# Motor_Interface.net
KiCad netlist of a schematic drawn in Altium Designer
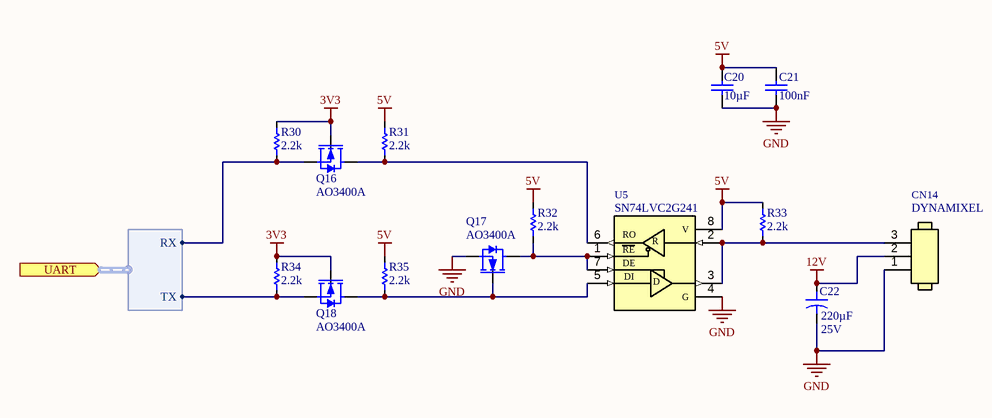
[diagram p0: Motor Interface.SchDoc]

(export (version "E")
  (design (tool "Eeschema 10.0.6"))
  (components
    (comp (ref "C20")
      (value "10µF")
      (footprint "CAP_CHIP_0603")
      (description "0603 Multilayer Ceramic Capacitors MLCC")
      (fields (field (name "PARTNUMBER") "CL10A106MA8NRNC") (field (name "TOLERANCE") "20%"))
      (libsource (lib "Sainsbury Wellcome Centre") (part "Cap"))
    )
    (comp (ref "C21")
      (value "100nF")
      (footprint "CAP_CHIP_0603")
      (description "0603 Multilayer Ceramic Capacitors MLCC")
      (fields (field (name "TOLERANCE") "10%") (field (name "PARTNUMBER") "CC0603KRX7R9BB104"))
      (libsource (lib "Sainsbury Wellcome Centre") (part "Cap"))
    )
    (comp (ref "C22")
      (value "220µF")
      (footprint "ECAP_SMD_6.3")
      (description "25V 220uF ±20% SMD,D6.3xL7.7mm Solid Capacitors")
      (fields
        (field (name "VOLTAGE RATING") "25V")
        (field (name "PARTNUMBER") "HV1E477M0810PZ")
        (field (name "TOLERANCE") "20%")
      )
      (libsource (lib "Sainsbury Wellcome Centre") (part "Cap Pol 2"))
    )
    (comp (ref "CN14")
      (value "DYNAMIXEL")
      (footprint "EH_90_1X3P")
      (description "Conn Shrouded Header (3 Sides) HDR 3 POS 2.5mm Solder RA Side Entry Thru-Hole Box")
      (fields (field (name "PARTNUMBER") "S3B-EH(LF)(SN)"))
      (libsource (lib "Sainsbury Wellcome Centre") (part "Wire to Board 1x3"))
    )
    (comp (ref "Q16")
      (value "AO3400A")
      (footprint "SOT23")
      (description "30V 5.7A 26.5mΩ@10V,5.7A 1.4W 1.5V@250uA 1 NChannel SOT-23-3L MOSFETs")
      (fields (field (name "PARTNUMBER") "AO3400A"))
      (libsource (lib "Sainsbury Wellcome Centre") (part "NMOS"))
    )
    (comp (ref "Q17")
      (value "AO3400A")
      (footprint "SOT23")
      (description "30V 5.7A 26.5mΩ@10V,5.7A 1.4W 1.5V@250uA 1 NChannel SOT-23-3L MOSFETs")
      (fields (field (name "PARTNUMBER") "AO3400A"))
      (libsource (lib "Sainsbury Wellcome Centre") (part "NMOS"))
    )
    (comp (ref "Q18")
      (value "AO3400A")
      (footprint "SOT23")
      (description "30V 5.7A 26.5mΩ@10V,5.7A 1.4W 1.5V@250uA 1 NChannel SOT-23-3L MOSFETs")
      (fields (field (name "PARTNUMBER") "AO3400A"))
      (libsource (lib "Sainsbury Wellcome Centre") (part "NMOS"))
    )
    (comp (ref "R30")
      (value "2.2k")
      (footprint "RES_CHIP_0603")
      (description "100mW Thick Film Resistors 75V ±100ppm/℃ ±1% 0603 Chip Resistor")
      (fields (field (name "PARTNUMBER") "0603WAF2201T5E") (field (name "TOLERANCE") "1%"))
      (libsource (lib "Sainsbury Wellcome Centre") (part "Res"))
    )
    (comp (ref "R31")
      (value "2.2k")
      (footprint "RES_CHIP_0603")
      (description "100mW Thick Film Resistors 75V ±100ppm/℃ ±1% 0603 Chip Resistor")
      (fields (field (name "PARTNUMBER") "0603WAF2201T5E") (field (name "TOLERANCE") "1%"))
      (libsource (lib "Sainsbury Wellcome Centre") (part "Res"))
    )
    (comp (ref "R32")
      (value "2.2k")
      (footprint "RES_CHIP_0603")
      (description "100mW Thick Film Resistors 75V ±100ppm/℃ ±1% 0603 Chip Resistor")
      (fields (field (name "PARTNUMBER") "0603WAF2201T5E") (field (name "TOLERANCE") "1%"))
      (libsource (lib "Sainsbury Wellcome Centre") (part "Res"))
    )
    (comp (ref "R33")
      (value "2.2k")
      (footprint "RES_CHIP_0603")
      (description "100mW Thick Film Resistors 75V ±100ppm/℃ ±1% 0603 Chip Resistor")
      (fields (field (name "PARTNUMBER") "0603WAF2201T5E") (field (name "TOLERANCE") "1%"))
      (libsource (lib "Sainsbury Wellcome Centre") (part "Res"))
    )
    (comp (ref "R34")
      (value "2.2k")
      (footprint "RES_CHIP_0603")
      (description "100mW Thick Film Resistors 75V ±100ppm/℃ ±1% 0603 Chip Resistor")
      (fields (field (name "PARTNUMBER") "0603WAF2201T5E") (field (name "TOLERANCE") "1%"))
      (libsource (lib "Sainsbury Wellcome Centre") (part "Res"))
    )
    (comp (ref "R35")
      (value "2.2k")
      (footprint "RES_CHIP_0603")
      (description "100mW Thick Film Resistors 75V ±100ppm/℃ ±1% 0603 Chip Resistor")
      (fields (field (name "PARTNUMBER") "0603WAF2201T5E") (field (name "TOLERANCE") "1%"))
      (libsource (lib "Sainsbury Wellcome Centre") (part "Res"))
    )
    (comp (ref "U5")
      (value "SN74LVC2G241")
      (footprint "VSSOP8_2X2.3_0.5E")
      (description "Buffer/Line Driver 2-CH Non-Inverting 3-ST CMOS 8-Pin VSSOP T/R")
      (fields (field (name "PARTNUMBER") "SN74LVC2G241DCUR"))
      (libsource (lib "Sainsbury Wellcome Centre") (part "SN74LVC2G241"))
    )
  )
  (nets
    (net (code "3") (name "3V3") (class "Default")
      (node (ref "Q16") (pin "1") (pinfunction "G_1") (pintype "passive"))
      (node (ref "Q18") (pin "1") (pinfunction "G_1") (pintype "passive"))
      (node (ref "R30") (pin "2") (pinfunction "2_2") (pintype "passive"))
      (node (ref "R34") (pin "2") (pinfunction "2_2") (pintype "passive"))
    )
    (net (code "4") (name "5V") (class "Default")
      (node (ref "C20") (pin "2") (pinfunction "2_2") (pintype "passive"))
      (node (ref "C21") (pin "2") (pinfunction "2_2") (pintype "passive"))
      (node (ref "R31") (pin "2") (pinfunction "2_2") (pintype "passive"))
      (node (ref "R32") (pin "2") (pinfunction "2_2") (pintype "passive"))
      (node (ref "R33") (pin "2") (pinfunction "2_2") (pintype "passive"))
      (node (ref "R35") (pin "2") (pinfunction "2_2") (pintype "passive"))
      (node (ref "U5") (pin "8") (pinfunction "V_8") (pintype "power_in"))
    )
    (net (code "5") (name "12V") (class "Default")
      (node (ref "C22") (pin "1") (pinfunction "1_1") (pintype "passive"))
      (node (ref "CN14") (pin "2") (pinfunction "2_2") (pintype "passive"))
    )
    (net (code "6") (name "GND") (class "Default")
      (node (ref "C20") (pin "1") (pinfunction "1_1") (pintype "passive"))
      (node (ref "C21") (pin "1") (pinfunction "1_1") (pintype "passive"))
      (node (ref "C22") (pin "2") (pinfunction "2_2") (pintype "passive"))
      (node (ref "CN14") (pin "1") (pinfunction "1_1") (pintype "passive"))
      (node (ref "Q17") (pin "2") (pinfunction "S_2") (pintype "passive"))
      (node (ref "U5") (pin "4") (pinfunction "G_4") (pintype "power_in"))
    )
    (net (code "7") (name "Net-(Q16-D)") (class "Default")
      (node (ref "Q16") (pin "3") (pinfunction "D_3") (pintype "passive"))
      (node (ref "R31") (pin "1") (pinfunction "1_1") (pintype "passive"))
      (node (ref "U5") (pin "6") (pinfunction "1Y_6") (pintype "output"))
    )
    (net (code "8") (name "Net-(Q16-S)") (class "Default")
      (node (ref "Q16") (pin "2") (pinfunction "S_2") (pintype "passive"))
      (node (ref "R30") (pin "1") (pinfunction "1_1") (pintype "passive"))
    )
    (net (code "9") (name "Net-(Q17-D)") (class "Default")
      (node (ref "Q17") (pin "3") (pinfunction "D_3") (pintype "passive"))
      (node (ref "R32") (pin "1") (pinfunction "1_1") (pintype "passive"))
      (node (ref "U5") (pin "1") (pinfunction "~{1OE}_1") (pintype "input"))
      (node (ref "U5") (pin "7") (pinfunction "2OE_7") (pintype "input"))
    )
    (net (code "10") (name "Net-(Q17-G)") (class "Default")
      (node (ref "Q17") (pin "1") (pinfunction "G_1") (pintype "passive"))
      (node (ref "Q18") (pin "3") (pinfunction "D_3") (pintype "passive"))
      (node (ref "R35") (pin "1") (pinfunction "1_1") (pintype "passive"))
      (node (ref "U5") (pin "5") (pinfunction "D_5") (pintype "input"))
    )
    (net (code "11") (name "Net-(Q18-S)") (class "Default")
      (node (ref "Q18") (pin "2") (pinfunction "S_2") (pintype "passive"))
      (node (ref "R34") (pin "1") (pinfunction "1_1") (pintype "passive"))
    )
    (net (code "12") (name "Net-(U5-1A)") (class "Default")
      (node (ref "CN14") (pin "3") (pinfunction "3_3") (pintype "passive"))
      (node (ref "R33") (pin "1") (pinfunction "1_1") (pintype "passive"))
      (node (ref "U5") (pin "2") (pinfunction "1A_2") (pintype "input"))
      (node (ref "U5") (pin "3") (pinfunction "B_3") (pintype "output"))
    )
  )
)
